# M1701D.net
KiCad netlist of a schematic drawn in EAGLE
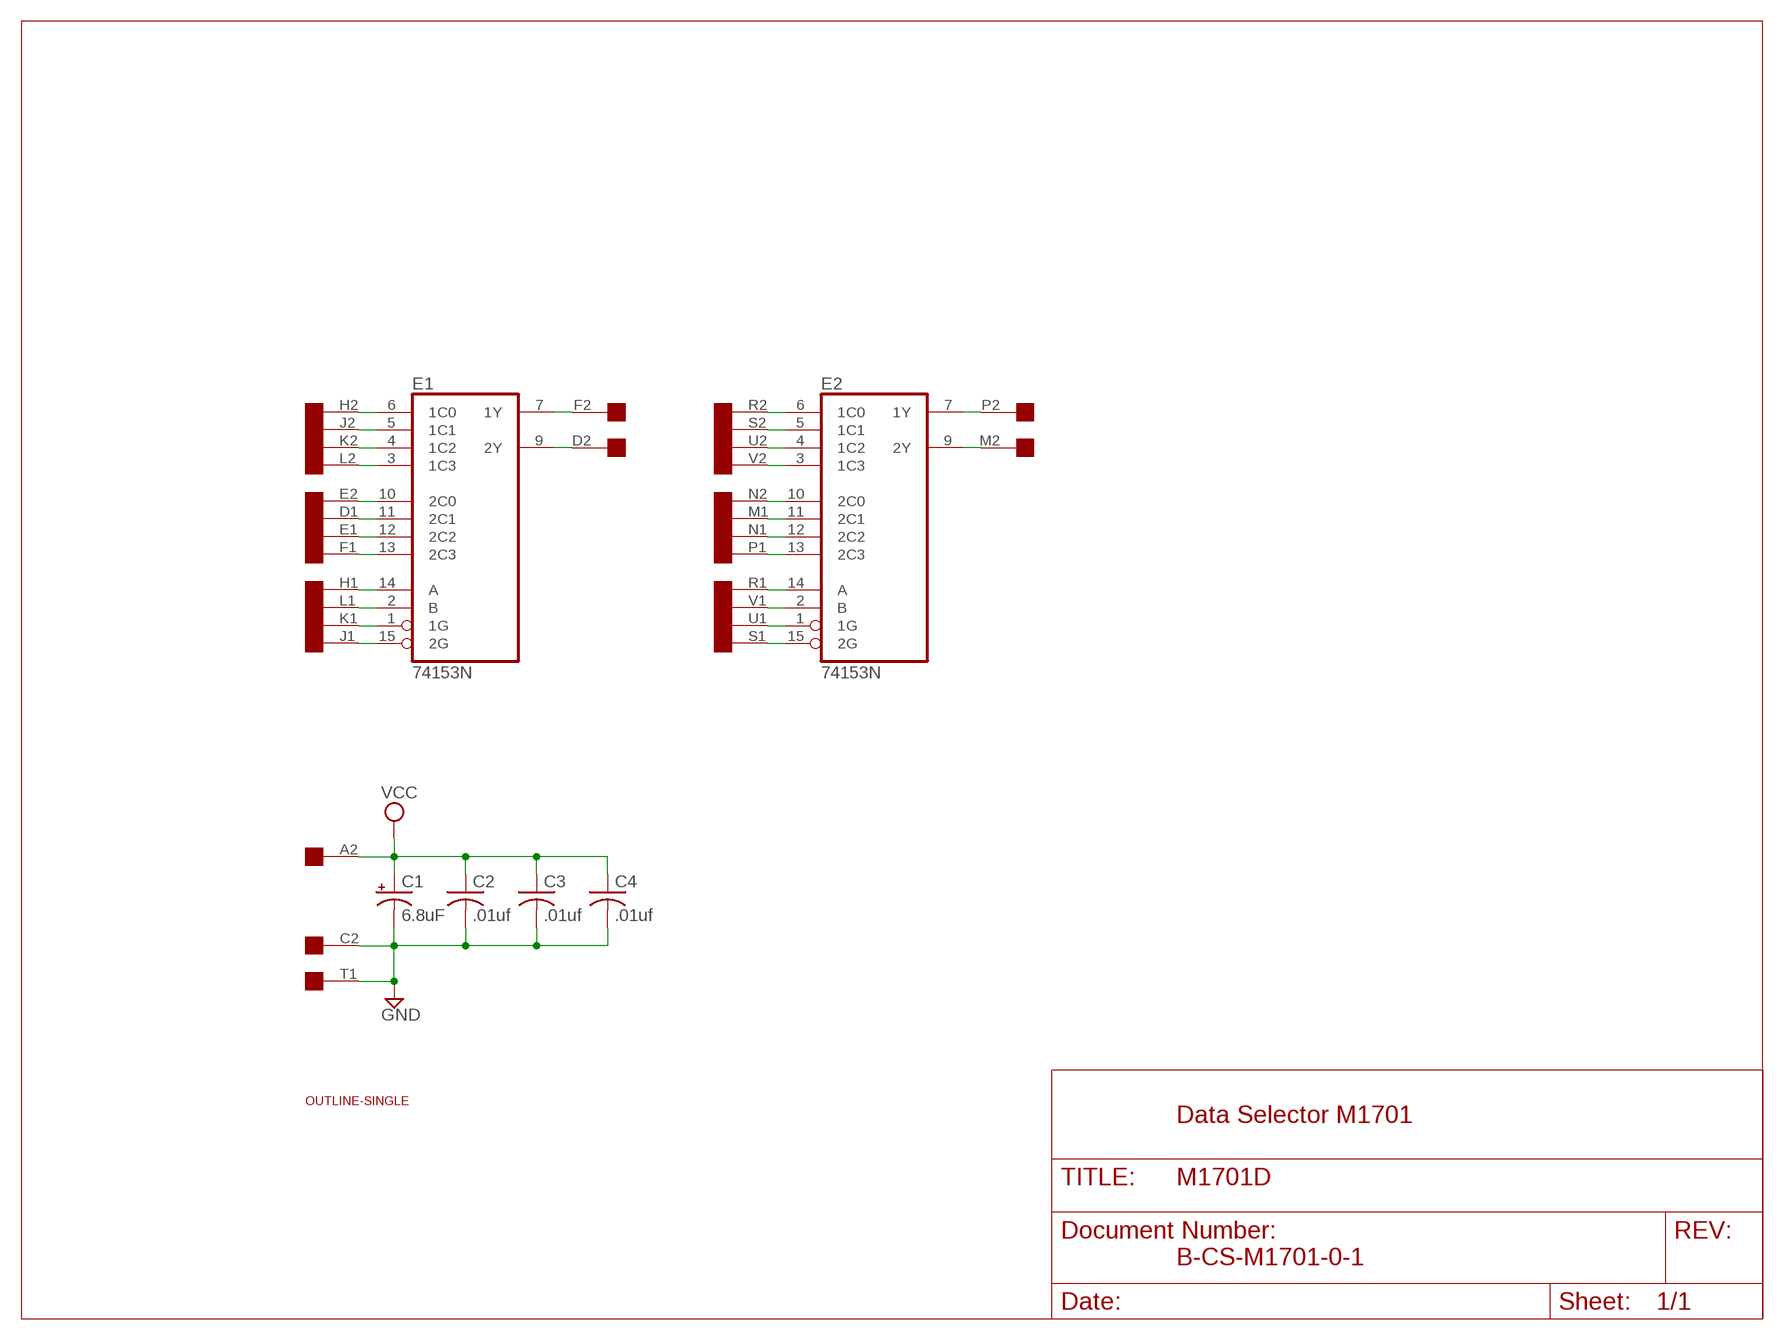
[diagram p0: schematic, sheet 1]

(export (version "E")
  (design (tool "Eeschema 10.0.6"))
  (components
    (comp (ref "C1")
      (value "6.8uF")
      (footprint "eagle-import:E12-8")
      (libsource (lib "eagle-import") (part "CPOL-USE20-8AXIAL"))
    )
    (comp (ref "C2")
      (value ".01uf")
      (footprint "eagle-import:C050-025X075")
      (libsource (lib "eagle-import") (part "C-US050-025X075"))
    )
    (comp (ref "C3")
      (value ".01uf")
      (footprint "eagle-import:C050-025X075")
      (libsource (lib "eagle-import") (part "C-US050-025X075"))
    )
    (comp (ref "C4")
      (value ".01uf")
      (footprint "eagle-import:C050-025X075")
      (libsource (lib "eagle-import") (part "C-US050-025X075"))
    )
    (comp (ref "E1")
      (value "74153N")
      (footprint "eagle-import:DIL16")
      (libsource (lib "eagle-import") (part "74153NS"))
    )
    (comp (ref "E2")
      (value "74153N")
      (footprint "eagle-import:DIL16")
      (libsource (lib "eagle-import") (part "74153NS"))
    )
    (comp (ref "U$1")
      (value "OUTLINE-SINGLE")
      (footprint "eagle-import:SINGLE")
      (libsource (lib "eagle-import") (part "OUTLINE-SINGLE"))
    )
    (comp (ref "U$2")
      (value "SINGLE")
      (footprint "eagle-import:EDGE-CON2")
      (libsource (lib "eagle-import") (part "SINGLE"))
    )
  )
  (nets
    (net (code "1") (name "GND") (class "Default")
      (node (ref "C1") (pin "-") (pinfunction "-_-") (pintype "passive"))
      (node (ref "C2") (pin "2") (pinfunction "2_2") (pintype "passive"))
      (node (ref "C3") (pin "2") (pinfunction "2_2") (pintype "passive"))
      (node (ref "C4") (pin "2") (pinfunction "2_2") (pintype "passive"))
      (node (ref "U$2") (pin "C2") (pinfunction "1_C2") (pintype "bidirectional"))
      (node (ref "U$2") (pin "T1") (pinfunction "1_T1") (pintype "bidirectional"))
    )
    (net (code "2") (name "Net-(E1A-1C0)") (class "Default")
      (node (ref "E1") (pin "6") (pinfunction "1C0_6") (pintype "input"))
      (node (ref "U$2") (pin "H2") (pinfunction "1_H2") (pintype "bidirectional"))
    )
    (net (code "3") (name "Net-(E1A-1C1)") (class "Default")
      (node (ref "E1") (pin "5") (pinfunction "1C1_5") (pintype "input"))
      (node (ref "U$2") (pin "J2") (pinfunction "1_J2") (pintype "bidirectional"))
    )
    (net (code "4") (name "Net-(E1A-1C2)") (class "Default")
      (node (ref "E1") (pin "4") (pinfunction "1C2_4") (pintype "input"))
      (node (ref "U$2") (pin "K2") (pinfunction "1_K2") (pintype "bidirectional"))
    )
    (net (code "5") (name "Net-(E1A-1C3)") (class "Default")
      (node (ref "E1") (pin "3") (pinfunction "1C3_3") (pintype "input"))
      (node (ref "U$2") (pin "L2") (pinfunction "1_L2") (pintype "bidirectional"))
    )
    (net (code "6") (name "Net-(E1A-1G)") (class "Default")
      (node (ref "E1") (pin "1") (pinfunction "1G_1") (pintype "input"))
      (node (ref "U$2") (pin "K1") (pinfunction "1_K1") (pintype "bidirectional"))
    )
    (net (code "7") (name "Net-(E1A-1Y)") (class "Default")
      (node (ref "E1") (pin "7") (pinfunction "1Y_7") (pintype "output"))
      (node (ref "U$2") (pin "F2") (pinfunction "1_F2") (pintype "bidirectional"))
    )
    (net (code "8") (name "Net-(E1A-2C0)") (class "Default")
      (node (ref "E1") (pin "10") (pinfunction "2C0_10") (pintype "input"))
      (node (ref "U$2") (pin "E2") (pinfunction "1_E2") (pintype "bidirectional"))
    )
    (net (code "9") (name "Net-(E1A-2C1)") (class "Default")
      (node (ref "E1") (pin "11") (pinfunction "2C1_11") (pintype "input"))
      (node (ref "U$2") (pin "D1") (pinfunction "1_D1") (pintype "bidirectional"))
    )
    (net (code "10") (name "Net-(E1A-2C2)") (class "Default")
      (node (ref "E1") (pin "12") (pinfunction "2C2_12") (pintype "input"))
      (node (ref "U$2") (pin "E1") (pinfunction "1_E1") (pintype "bidirectional"))
    )
    (net (code "11") (name "Net-(E1A-2C3)") (class "Default")
      (node (ref "E1") (pin "13") (pinfunction "2C3_13") (pintype "input"))
      (node (ref "U$2") (pin "F1") (pinfunction "1_F1") (pintype "bidirectional"))
    )
    (net (code "12") (name "Net-(E1A-2G)") (class "Default")
      (node (ref "E1") (pin "15") (pinfunction "2G_15") (pintype "input"))
      (node (ref "U$2") (pin "J1") (pinfunction "1_J1") (pintype "bidirectional"))
    )
    (net (code "13") (name "Net-(E1A-2Y)") (class "Default")
      (node (ref "E1") (pin "9") (pinfunction "2Y_9") (pintype "output"))
      (node (ref "U$2") (pin "D2") (pinfunction "1_D2") (pintype "bidirectional"))
    )
    (net (code "14") (name "Net-(E1A-A)") (class "Default")
      (node (ref "E1") (pin "14") (pinfunction "A_14") (pintype "input"))
      (node (ref "U$2") (pin "H1") (pinfunction "1_H1") (pintype "bidirectional"))
    )
    (net (code "15") (name "Net-(E1A-B)") (class "Default")
      (node (ref "E1") (pin "2") (pinfunction "B_2") (pintype "input"))
      (node (ref "U$2") (pin "L1") (pinfunction "1_L1") (pintype "bidirectional"))
    )
    (net (code "16") (name "Net-(E2A-1C0)") (class "Default")
      (node (ref "E2") (pin "6") (pinfunction "1C0_6") (pintype "input"))
      (node (ref "U$2") (pin "R2") (pinfunction "1_R2") (pintype "bidirectional"))
    )
    (net (code "17") (name "Net-(E2A-1C1)") (class "Default")
      (node (ref "E2") (pin "5") (pinfunction "1C1_5") (pintype "input"))
      (node (ref "U$2") (pin "S2") (pinfunction "1_S2") (pintype "bidirectional"))
    )
    (net (code "18") (name "Net-(E2A-1C2)") (class "Default")
      (node (ref "E2") (pin "4") (pinfunction "1C2_4") (pintype "input"))
      (node (ref "U$2") (pin "U2") (pinfunction "1_U2") (pintype "bidirectional"))
    )
    (net (code "19") (name "Net-(E2A-1C3)") (class "Default")
      (node (ref "E2") (pin "3") (pinfunction "1C3_3") (pintype "input"))
      (node (ref "U$2") (pin "V2") (pinfunction "1_V2") (pintype "bidirectional"))
    )
    (net (code "20") (name "Net-(E2A-1G)") (class "Default")
      (node (ref "E2") (pin "1") (pinfunction "1G_1") (pintype "input"))
      (node (ref "U$2") (pin "U1") (pinfunction "1_U1") (pintype "bidirectional"))
    )
    (net (code "21") (name "Net-(E2A-1Y)") (class "Default")
      (node (ref "E2") (pin "7") (pinfunction "1Y_7") (pintype "output"))
      (node (ref "U$2") (pin "P2") (pinfunction "1_P2") (pintype "bidirectional"))
    )
    (net (code "22") (name "Net-(E2A-2C0)") (class "Default")
      (node (ref "E2") (pin "10") (pinfunction "2C0_10") (pintype "input"))
      (node (ref "U$2") (pin "N2") (pinfunction "1_N2") (pintype "bidirectional"))
    )
    (net (code "23") (name "Net-(E2A-2C1)") (class "Default")
      (node (ref "E2") (pin "11") (pinfunction "2C1_11") (pintype "input"))
      (node (ref "U$2") (pin "M1") (pinfunction "1_M1") (pintype "bidirectional"))
    )
    (net (code "24") (name "Net-(E2A-2C2)") (class "Default")
      (node (ref "E2") (pin "12") (pinfunction "2C2_12") (pintype "input"))
      (node (ref "U$2") (pin "N1") (pinfunction "1_N1") (pintype "bidirectional"))
    )
    (net (code "25") (name "Net-(E2A-2C3)") (class "Default")
      (node (ref "E2") (pin "13") (pinfunction "2C3_13") (pintype "input"))
      (node (ref "U$2") (pin "P1") (pinfunction "1_P1") (pintype "bidirectional"))
    )
    (net (code "26") (name "Net-(E2A-2G)") (class "Default")
      (node (ref "E2") (pin "15") (pinfunction "2G_15") (pintype "input"))
      (node (ref "U$2") (pin "S1") (pinfunction "1_S1") (pintype "bidirectional"))
    )
    (net (code "27") (name "Net-(E2A-2Y)") (class "Default")
      (node (ref "E2") (pin "9") (pinfunction "2Y_9") (pintype "output"))
      (node (ref "U$2") (pin "M2") (pinfunction "1_M2") (pintype "bidirectional"))
    )
    (net (code "28") (name "Net-(E2A-A)") (class "Default")
      (node (ref "E2") (pin "14") (pinfunction "A_14") (pintype "input"))
      (node (ref "U$2") (pin "R1") (pinfunction "1_R1") (pintype "bidirectional"))
    )
    (net (code "29") (name "Net-(E2A-B)") (class "Default")
      (node (ref "E2") (pin "2") (pinfunction "B_2") (pintype "input"))
      (node (ref "U$2") (pin "V1") (pinfunction "1_V1") (pintype "bidirectional"))
    )
    (net (code "30") (name "VCC") (class "Default")
      (node (ref "C1") (pin "+") (pinfunction "+_+") (pintype "passive"))
      (node (ref "C2") (pin "1") (pinfunction "1_1") (pintype "passive"))
      (node (ref "C3") (pin "1") (pinfunction "1_1") (pintype "passive"))
      (node (ref "C4") (pin "1") (pinfunction "1_1") (pintype "passive"))
      (node (ref "U$2") (pin "A2") (pinfunction "1_A2") (pintype "bidirectional"))
    )
  )
)
